# 11-Power.net
KiCad netlist of a schematic drawn in Altium Designer
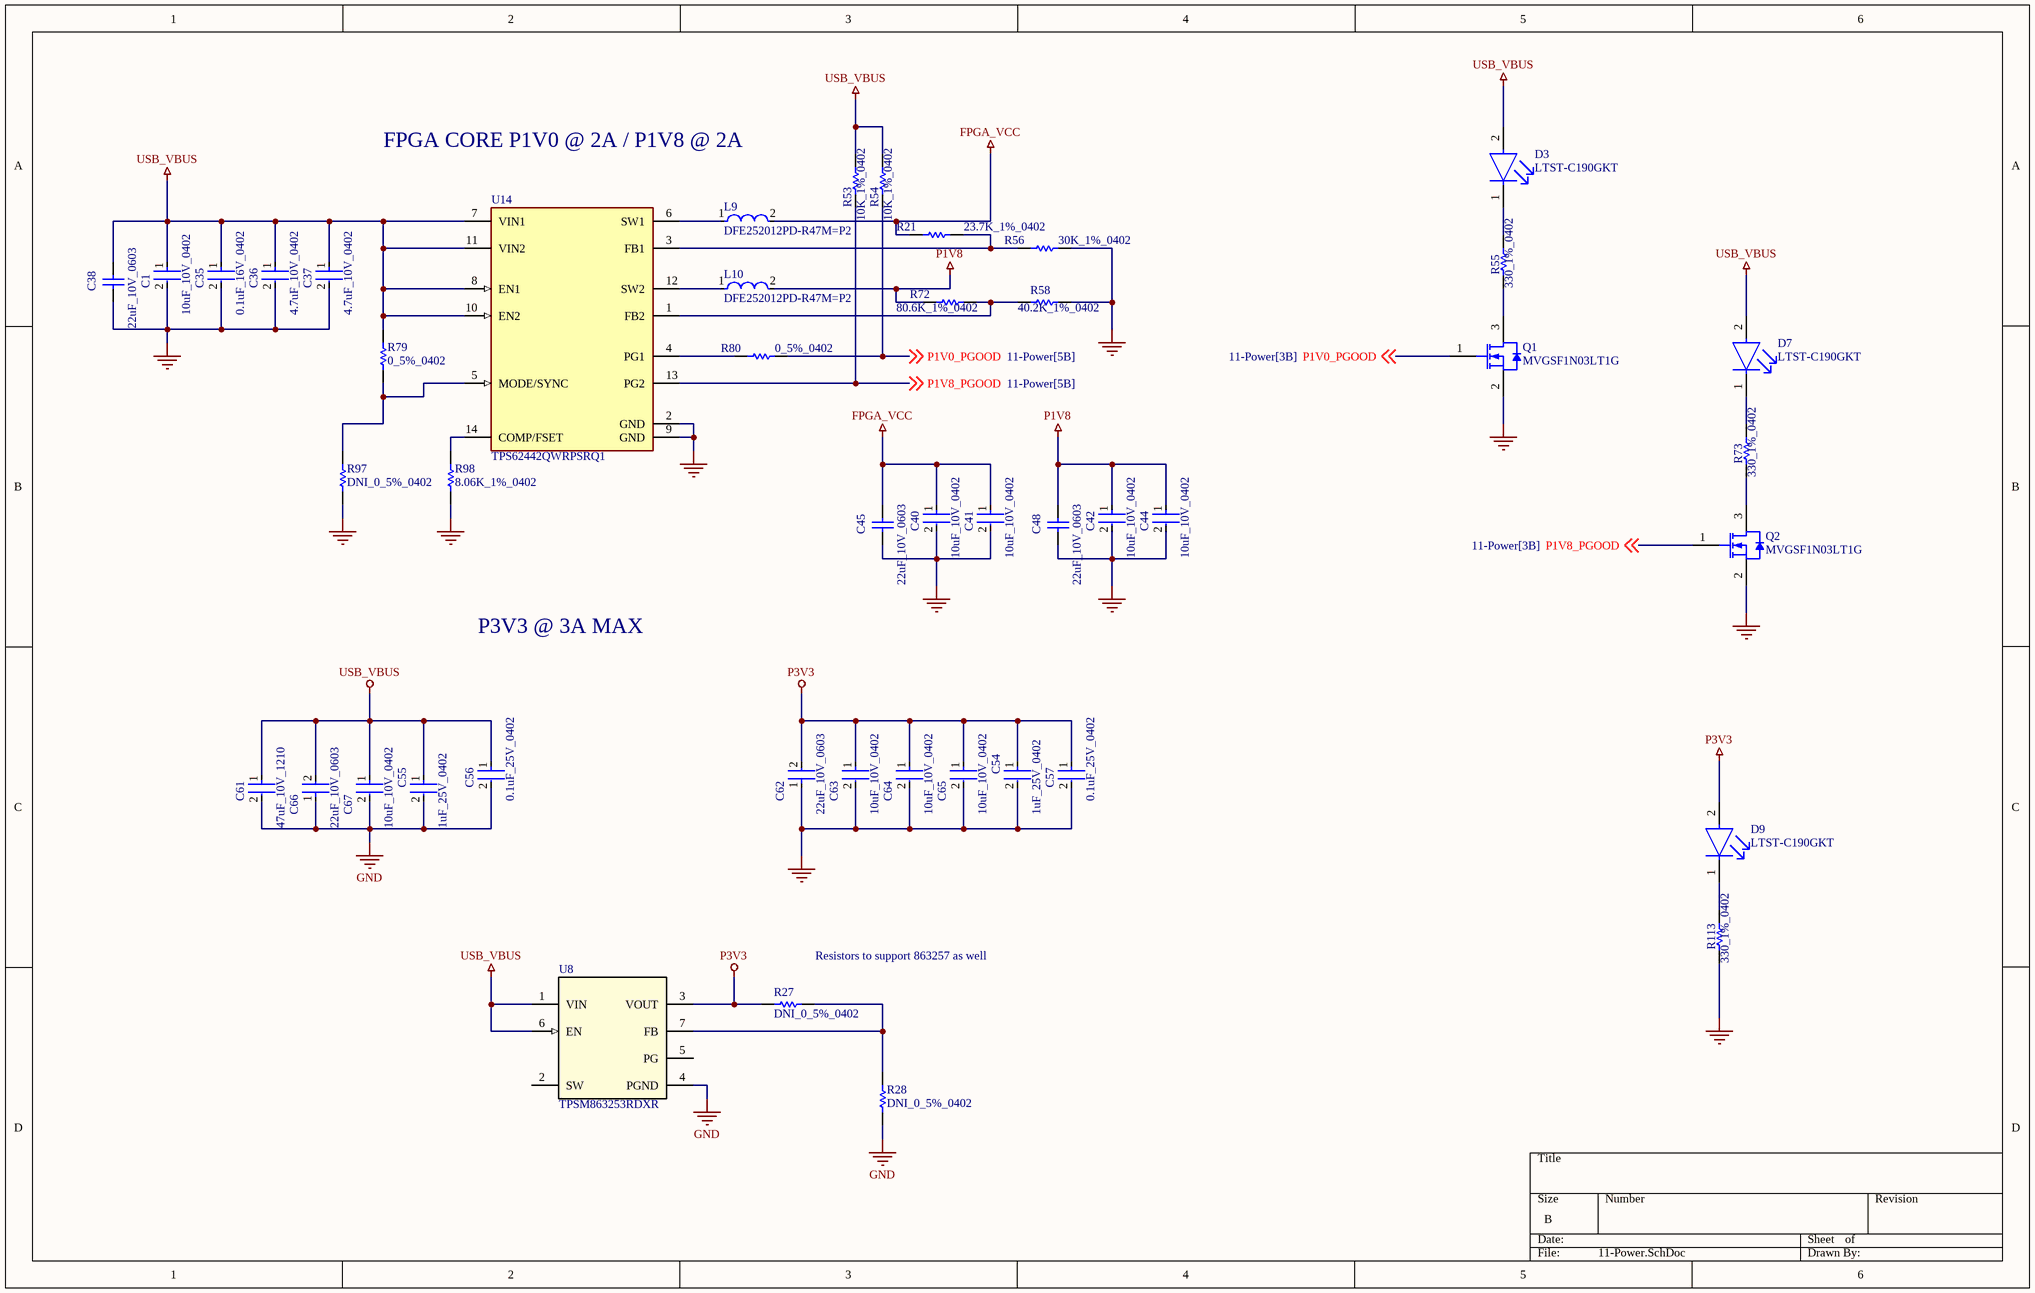
[diagram p0: 11-Power.SchDoc]

(export (version "E")
  (design (tool "Eeschema 10.0.6"))
  (components
    (comp (ref "C1")
      (value "10uF_10V_0402")
      (footprint "FP-CL05A106MP5NUNC-MFG")
      (description "CAP CER 10UF 10V X5R 0402")
      (fields
        (field (name "OCTOPART") "https://octopart.com/cl05a106mp5nunc-samsung-22457395")
        (field (name "TOLERANCE") "20%")
      )
      (libsource (lib "Altium Content Vault") (part "b4654b650e69147ec39a6b967a45e02"))
    )
    (comp (ref "C35")
      (value "0.1uF_16V_0402")
      (footprint "FP-C0402-BB-MFG")
      (description "CAP CER 0.1UF 16V 5% X7R 0402")
      (fields
        (field (name "MANUFACTURER") "Kemet")
        (field (name "MANUFACTURER PART NUMBER") "C0402C104J4RACTU")
      )
      (libsource (lib "Altium Content Vault") (part "b4654b650e69147ec39a6b967a45e02"))
    )
    (comp (ref "C36")
      (value "4.7uF_10V_0402")
      (footprint "FP-C1005-050-0_15-MFG")
      (description "CAP CER 4.7UF 10V X5R 0402")
      (fields (field (name "TOLERANCE") "10%"))
      (libsource (lib "Altium Content Vault") (part "b4654b650e69147ec39a6b967a45e02"))
    )
    (comp (ref "C37")
      (value "4.7uF_10V_0402")
      (footprint "FP-C1005-050-0_15-MFG")
      (description "CAP CER 4.7UF 10V X5R 0402")
      (fields (field (name "TOLERANCE") "10%"))
      (libsource (lib "Altium Content Vault") (part "b4654b650e69147ec39a6b967a45e02"))
    )
    (comp (ref "C38")
      (value "22uF_10V_0603")
      (footprint "CAPC1608X100X20ML10")
      (description "Chip Capacitor, 22 uF, +/- 20%, 10 V, -55 to 85 degC, 0603 (1608 Metric), RoHS, Tape and Reel")
      (fields (field (name "MANUFACTURER") "TDK") (field (name "TOLERANCE") "±20%"))
      (libsource (lib "Altium Content Vault") (part "CAP-NP-2"))
    )
    (comp (ref "C40")
      (value "10uF_10V_0402")
      (footprint "FP-CL05A106MP5NUNC-MFG")
      (description "CAP CER 10UF 10V X5R 0402")
      (fields
        (field (name "OCTOPART") "https://octopart.com/cl05a106mp5nunc-samsung-22457395")
        (field (name "TOLERANCE") "20%")
      )
      (libsource (lib "Altium Content Vault") (part "b4654b650e69147ec39a6b967a45e02"))
    )
    (comp (ref "C41")
      (value "10uF_10V_0402")
      (footprint "FP-CL05A106MP5NUNC-MFG")
      (description "CAP CER 10UF 10V X5R 0402")
      (fields
        (field (name "OCTOPART") "https://octopart.com/cl05a106mp5nunc-samsung-22457395")
        (field (name "TOLERANCE") "20%")
      )
      (libsource (lib "Altium Content Vault") (part "b4654b650e69147ec39a6b967a45e02"))
    )
    (comp (ref "C42")
      (value "10uF_10V_0402")
      (footprint "FP-CL05A106MP5NUNC-MFG")
      (description "CAP CER 10UF 10V X5R 0402")
      (fields
        (field (name "OCTOPART") "https://octopart.com/cl05a106mp5nunc-samsung-22457395")
        (field (name "TOLERANCE") "20%")
      )
      (libsource (lib "Altium Content Vault") (part "b4654b650e69147ec39a6b967a45e02"))
    )
    (comp (ref "C44")
      (value "10uF_10V_0402")
      (footprint "FP-CL05A106MP5NUNC-MFG")
      (description "CAP CER 10UF 10V X5R 0402")
      (fields
        (field (name "OCTOPART") "https://octopart.com/cl05a106mp5nunc-samsung-22457395")
        (field (name "TOLERANCE") "20%")
      )
      (libsource (lib "Altium Content Vault") (part "b4654b650e69147ec39a6b967a45e02"))
    )
    (comp (ref "C45")
      (value "22uF_10V_0603")
      (footprint "CAPC1608X100X20ML10")
      (description "Chip Capacitor, 22 uF, +/- 20%, 10 V, -55 to 85 degC, 0603 (1608 Metric), RoHS, Tape and Reel")
      (fields (field (name "MANUFACTURER") "TDK") (field (name "TOLERANCE") "±20%"))
      (libsource (lib "Altium Content Vault") (part "CAP-NP-2"))
    )
    (comp (ref "C48")
      (value "22uF_10V_0603")
      (footprint "CAPC1608X100X20ML10")
      (description "Chip Capacitor, 22 uF, +/- 20%, 10 V, -55 to 85 degC, 0603 (1608 Metric), RoHS, Tape and Reel")
      (fields (field (name "MANUFACTURER") "TDK") (field (name "TOLERANCE") "±20%"))
      (libsource (lib "Altium Content Vault") (part "CAP-NP-2"))
    )
    (comp (ref "C54")
      (value "1uF_25V_0402")
      (footprint "FP-C1005-050-0_05-IPC_B")
      (description "Multilayer Ceramic Capacitors 1μF ±10% 25V X5R SMD 0402")
      (fields (field (name "TOLERANCE") "10%"))
      (libsource (lib "Altium Content Vault") (part "b4654b650e69147ec39a6b967a45e02"))
    )
    (comp (ref "C55")
      (value "1uF_25V_0402")
      (footprint "FP-C1005-050-0_05-IPC_B")
      (description "Multilayer Ceramic Capacitors 1μF ±10% 25V X5R SMD 0402")
      (fields (field (name "TOLERANCE") "10%"))
      (libsource (lib "Altium Content Vault") (part "b4654b650e69147ec39a6b967a45e02"))
    )
    (comp (ref "C56")
      (value "0.1uF_25V_0402")
      (footprint "FP-0402-L_1_0_0_05-W_0_5-IPC_B")
      (description "None")
      (fields (field (name "TOLERANCE") "10%") (field (name "VOLTAGE") "25V"))
      (libsource (lib "Altium Content Vault") (part "b4654b650e69147ec39a6b967a45e02"))
    )
    (comp (ref "C57")
      (value "0.1uF_25V_0402")
      (footprint "FP-0402-L_1_0_0_05-W_0_5-IPC_B")
      (description "None")
      (fields (field (name "TOLERANCE") "10%") (field (name "VOLTAGE") "25V"))
      (libsource (lib "Altium Content Vault") (part "b4654b650e69147ec39a6b967a45e02"))
    )
    (comp (ref "C61")
      (value "47uF_10V_1210")
      (footprint "FP-MK325M-MFG")
      (description "CAP CER 47UF 10V X7R 1210")
      (fields (field (name "TOLERANCE") "20%") (field (name "VOLTAGE") "10V"))
      (libsource (lib "Altium Content Vault") (part "b4654b650e69147ec39a6b967a45e02"))
    )
    (comp (ref "C62")
      (value "22uF_10V_0603")
      (footprint "FP-GRM188-0_2-IPC_C")
      (description "Chip Multilayer Ceramic Capacitors for General Purpose, 0603, 22uF, X5R, 15%, 20%, 10V")
      (fields (field (name "TOLERANCE") "20%"))
      (libsource (lib "Altium Content Vault") (part "11868f565c42a9108669ba33697ecf6"))
    )
    (comp (ref "C63")
      (value "10uF_10V_0402")
      (footprint "FP-CL05A106MP5NUNC-MFG")
      (description "CAP CER 10UF 10V X5R 0402")
      (fields
        (field (name "OCTOPART") "https://octopart.com/cl05a106mp5nunc-samsung-22457395")
        (field (name "TOLERANCE") "20%")
      )
      (libsource (lib "Altium Content Vault") (part "b4654b650e69147ec39a6b967a45e02"))
    )
    (comp (ref "C64")
      (value "10uF_10V_0402")
      (footprint "FP-CL05A106MP5NUNC-MFG")
      (description "CAP CER 10UF 10V X5R 0402")
      (fields
        (field (name "OCTOPART") "https://octopart.com/cl05a106mp5nunc-samsung-22457395")
        (field (name "TOLERANCE") "20%")
      )
      (libsource (lib "Altium Content Vault") (part "b4654b650e69147ec39a6b967a45e02"))
    )
    (comp (ref "C65")
      (value "10uF_10V_0402")
      (footprint "FP-CL05A106MP5NUNC-MFG")
      (description "CAP CER 10UF 10V X5R 0402")
      (fields
        (field (name "OCTOPART") "https://octopart.com/cl05a106mp5nunc-samsung-22457395")
        (field (name "TOLERANCE") "20%")
      )
      (libsource (lib "Altium Content Vault") (part "b4654b650e69147ec39a6b967a45e02"))
    )
    (comp (ref "C66")
      (value "22uF_10V_0603")
      (footprint "FP-GRM188-0_2-IPC_C")
      (description "Chip Multilayer Ceramic Capacitors for General Purpose, 0603, 22uF, X5R, 15%, 20%, 10V")
      (fields (field (name "TOLERANCE") "20%"))
      (libsource (lib "Altium Content Vault") (part "11868f565c42a9108669ba33697ecf6"))
    )
    (comp (ref "C67")
      (value "10uF_10V_0402")
      (footprint "FP-CL05A106MP5NUNC-MFG")
      (description "CAP CER 10UF 10V X5R 0402")
      (fields
        (field (name "OCTOPART") "https://octopart.com/cl05a106mp5nunc-samsung-22457395")
        (field (name "TOLERANCE") "20%")
      )
      (libsource (lib "Altium Content Vault") (part "b4654b650e69147ec39a6b967a45e02"))
    )
    (comp (ref "D3")
      (value "LTST-C190GKT")
      (footprint "FP-LTST-C190GKT-MFG")
      (description "LED GREEN CLEAR CHIP SMD")
      (fields (field (name "VOLTAGE") "2V"))
      (libsource (lib "Altium Content Vault") (part "8706943c75ba83719d021d2fdc84c58"))
    )
    (comp (ref "D7")
      (value "LTST-C190GKT")
      (footprint "FP-LTST-C190GKT-MFG")
      (description "LED GREEN CLEAR CHIP SMD")
      (fields (field (name "VOLTAGE") "2V"))
      (libsource (lib "Altium Content Vault") (part "8706943c75ba83719d021d2fdc84c58"))
    )
    (comp (ref "D9")
      (value "LTST-C190GKT")
      (footprint "FP-LTST-C190GKT-MFG")
      (description "LED GREEN CLEAR CHIP SMD")
      (fields (field (name "VOLTAGE") "2V"))
      (libsource (lib "Altium Content Vault") (part "8706943c75ba83719d021d2fdc84c58"))
    )
    (comp (ref "L9")
      (value "DFE252012PD-R47M=P2")
      (footprint "FP-DFE252012C-IPC_A")
      (description "Shielded Wirewound Inductor 0.47uH 20% 4000mA 0.027Ω 1008 (2520)")
      (libsource (lib "Altium Content Vault") (part "725321dda6339637d4d059423bc1c3c"))
    )
    (comp (ref "L10")
      (value "DFE252012PD-R47M=P2")
      (footprint "FP-DFE252012C-IPC_A")
      (description "Shielded Wirewound Inductor 0.47uH 20% 4000mA 0.027Ω 1008 (2520)")
      (libsource (lib "Altium Content Vault") (part "725321dda6339637d4d059423bc1c3c"))
    )
    (comp (ref "Q1")
      (value "MVGSF1N03LT1G")
      (footprint "ONSC-SOT-23-3-318-08_V")
      (description "Power MOSFET, 30 V, 2.1 A, Single N-Channel, 3-Pin SOT-23, Pb-Free, Tape and Reel")
      (fields (field (name "MANUFACTURER") "On Semiconductor"))
      (libsource (lib "Altium Content Vault") (part "ONSC-NMOS-G1S2D3-3"))
    )
    (comp (ref "Q2")
      (value "MVGSF1N03LT1G")
      (footprint "ONSC-SOT-23-3-318-08_V")
      (description "Power MOSFET, 30 V, 2.1 A, Single N-Channel, 3-Pin SOT-23, Pb-Free, Tape and Reel")
      (fields (field (name "MANUFACTURER") "On Semiconductor"))
      (libsource (lib "Altium Content Vault") (part "ONSC-NMOS-G1S2D3-3"))
    )
    (comp (ref "R21")
      (value "23.7K_1%_0402")
      (footprint "RESC1005X40X25ML05T05")
      (fields (field (name "PART NUMBER") "CRCW040223K7FKED") (field (name "MANUFACTURER") "Vishay Dale"))
      (libsource (lib "Altium Content Vault") (part "RES"))
    )
    (comp (ref "R27")
      (value "DNI_0_5%_0402")
      (footprint "RESC1005X40X25NL05T10")
      (fields (field (name "MANUFACTURER") "Panasonic") (field (name "PART NUMBER") "ERJ-U020R00X"))
      (libsource (lib "Altium Content Vault") (part "RES"))
    )
    (comp (ref "R28")
      (value "DNI_0_5%_0402")
      (footprint "RESC1005X40X25NL05T10")
      (fields (field (name "MANUFACTURER") "Panasonic") (field (name "PART NUMBER") "ERJ-U020R00X"))
      (libsource (lib "Altium Content Vault") (part "RES"))
    )
    (comp (ref "R53")
      (value "10K_1%_0402")
      (footprint "RESC1005X40X25NL10T10")
      (fields (field (name "MANUFACTURER") "Bourns") (field (name "PART NUMBER") "CR0402-FX-1002GLF"))
      (libsource (lib "Altium Content Vault") (part "RES"))
    )
    (comp (ref "R54")
      (value "10K_1%_0402")
      (footprint "RESC1005X40X25NL10T10")
      (fields (field (name "MANUFACTURER") "Bourns") (field (name "PART NUMBER") "CR0402-FX-1002GLF"))
      (libsource (lib "Altium Content Vault") (part "RES"))
    )
    (comp (ref "R55")
      (value "330_1%_0402")
      (footprint "RESC1005X40X25NL10T10")
      (fields (field (name "MANUFACTURER") "Panasonic") (field (name "PART NUMBER") "ERA-2AED331X"))
      (libsource (lib "Altium Content Vault") (part "RES"))
    )
    (comp (ref "R56")
      (value "30K_1%_0402")
      (footprint "RESC1005X40X25ML05T05")
      (fields (field (name "PART NUMBER") "ERJ-2GEJ303X") (field (name "MANUFACTURER") "Panasonic"))
      (libsource (lib "Altium Content Vault") (part "RES"))
    )
    (comp (ref "R58")
      (value "40.2K_1%_0402")
      (footprint "RESC1005X40X25ML05T10")
      (fields (field (name "PART NUMBER") "RC0402FR-0740K2L") (field (name "MANUFACTURER") "Yageo / Phycomp"))
      (libsource (lib "Altium Content Vault") (part "RES"))
    )
    (comp (ref "R72")
      (value "80.6K_1%_0402")
      (footprint "RESC1005X40X25NL05T10")
      (fields (field (name "PART NUMBER") "RC0402FR-0780K6L") (field (name "MANUFACTURER") "Yageo / Phycomp"))
      (libsource (lib "Altium Content Vault") (part "RES"))
    )
    (comp (ref "R73")
      (value "330_1%_0402")
      (footprint "RESC1005X40X25NL10T10")
      (fields (field (name "MANUFACTURER") "Panasonic") (field (name "PART NUMBER") "ERA-2AED331X"))
      (libsource (lib "Altium Content Vault") (part "RES"))
    )
    (comp (ref "R79")
      (value "0_5%_0402")
      (footprint "RESC1005X40X25NL05T10")
      (fields (field (name "MANUFACTURER") "Panasonic") (field (name "PART NUMBER") "ERJ-U020R00X"))
      (libsource (lib "Altium Content Vault") (part "RES"))
    )
    (comp (ref "R80")
      (value "0_5%_0402")
      (footprint "RESC1005X40X25NL05T10")
      (fields (field (name "MANUFACTURER") "Panasonic") (field (name "PART NUMBER") "ERJ-U020R00X"))
      (libsource (lib "Altium Content Vault") (part "RES"))
    )
    (comp (ref "R97")
      (value "DNI_0_5%_0402")
      (footprint "RESC1005X40X25NL05T10")
      (fields (field (name "MANUFACTURER") "Panasonic") (field (name "PART NUMBER") "ERJ-U020R00X"))
      (libsource (lib "Altium Content Vault") (part "RES"))
    )
    (comp (ref "R98")
      (value "8.06K_1%_0402")
      (footprint "RESC1005X40X25ML05T05")
      (description "Chip Resistor, 8.06 KOhm, +/- 1%, 63 mW, -55 to 155 degC, 0402 (1005 Metric), RoHS, Tape and Reel")
      (fields (field (name "PARTNUMBER") "CRCW04028K06FKED") (field (name "TOLERANCE") "1%"))
      (libsource (lib "Altium Content Vault") (part "RES-2"))
    )
    (comp (ref "R113")
      (value "330_1%_0402")
      (footprint "RESC1005X40X25NL10T10")
      (fields (field (name "MANUFACTURER") "Panasonic") (field (name "PART NUMBER") "ERA-2AED331X"))
      (libsource (lib "Altium Content Vault") (part "RES"))
    )
    (comp (ref "U8")
      (value "TPSM863253RDXR")
      (footprint "RDX0007A-MFG")
      (description "No Description Available")
      (libsource (lib "TPSM863253RDXR") (part "TPSM863253RDXR"))
    )
    (comp (ref "U14")
      (value "TPS62442QWRPSRQ1")
      (footprint "FP-RQR0014A-MFG")
      (description "Adjustable-Frequency Dual Step-Down Converter, 2.7-6V VIN, 0.6-5.5V 2A VOUT, VQFN-HR14")
      (libsource (lib "Altium Content Vault") (part "72c5b9bb22caeb688b1070b758806aa"))
    )
  )
  (nets
    (net (code "1") (name "FPGA_VCC") (class "Default")
      (node (ref "C40") (pin "1") (pinfunction "1_1") (pintype "passive"))
      (node (ref "C41") (pin "1") (pinfunction "1_1") (pintype "passive"))
      (node (ref "C45") (pin "2") (pinfunction "2_2") (pintype "passive"))
      (node (ref "L9") (pin "2") (pinfunction "2_2") (pintype "passive"))
      (node (ref "R21") (pin "1") (pinfunction "1_1") (pintype "passive"))
    )
    (net (code "2") (name "GND") (class "Default")
      (node (ref "C1") (pin "2") (pinfunction "2_2") (pintype "passive"))
      (node (ref "C35") (pin "2") (pinfunction "2_2") (pintype "passive"))
      (node (ref "C36") (pin "2") (pinfunction "2_2") (pintype "passive"))
      (node (ref "C37") (pin "2") (pinfunction "2_2") (pintype "passive"))
      (node (ref "C38") (pin "1") (pinfunction "1_1") (pintype "passive"))
      (node (ref "C40") (pin "2") (pinfunction "2_2") (pintype "passive"))
      (node (ref "C41") (pin "2") (pinfunction "2_2") (pintype "passive"))
      (node (ref "C42") (pin "2") (pinfunction "2_2") (pintype "passive"))
      (node (ref "C44") (pin "2") (pinfunction "2_2") (pintype "passive"))
      (node (ref "C45") (pin "1") (pinfunction "1_1") (pintype "passive"))
      (node (ref "C48") (pin "1") (pinfunction "1_1") (pintype "passive"))
      (node (ref "C54") (pin "2") (pinfunction "2_2") (pintype "passive"))
      (node (ref "C55") (pin "2") (pinfunction "2_2") (pintype "passive"))
      (node (ref "C56") (pin "2") (pinfunction "2_2") (pintype "passive"))
      (node (ref "C57") (pin "2") (pinfunction "2_2") (pintype "passive"))
      (node (ref "C61") (pin "2") (pinfunction "2_2") (pintype "passive"))
      (node (ref "C62") (pin "1") (pinfunction "1_1") (pintype "passive"))
      (node (ref "C63") (pin "2") (pinfunction "2_2") (pintype "passive"))
      (node (ref "C64") (pin "2") (pinfunction "2_2") (pintype "passive"))
      (node (ref "C65") (pin "2") (pinfunction "2_2") (pintype "passive"))
      (node (ref "C66") (pin "1") (pinfunction "1_1") (pintype "passive"))
      (node (ref "C67") (pin "2") (pinfunction "2_2") (pintype "passive"))
      (node (ref "Q1") (pin "2") (pinfunction "S_2") (pintype "passive"))
      (node (ref "Q2") (pin "2") (pinfunction "S_2") (pintype "passive"))
      (node (ref "R113") (pin "1") (pinfunction "1_1") (pintype "passive"))
      (node (ref "R28") (pin "2") (pinfunction "2_2") (pintype "passive"))
      (node (ref "R56") (pin "2") (pinfunction "2_2") (pintype "passive"))
      (node (ref "R58") (pin "2") (pinfunction "2_2") (pintype "passive"))
      (node (ref "R97") (pin "1") (pinfunction "1_1") (pintype "passive"))
      (node (ref "R98") (pin "1") (pinfunction "1_1") (pintype "passive"))
      (node (ref "U14") (pin "2") (pinfunction "GND_2") (pintype "power_in"))
      (node (ref "U14") (pin "9") (pinfunction "GND_9") (pintype "power_in"))
      (node (ref "U8") (pin "4") (pinfunction "PGND_4") (pintype "power_in"))
    )
    (net (code "3") (name "Net-(D3-C)") (class "Default")
      (node (ref "D3") (pin "1") (pinfunction "C_1") (pintype "passive"))
      (node (ref "R55") (pin "2") (pinfunction "2_2") (pintype "passive"))
    )
    (net (code "4") (name "Net-(D7-C)") (class "Default")
      (node (ref "D7") (pin "1") (pinfunction "C_1") (pintype "passive"))
      (node (ref "R73") (pin "2") (pinfunction "2_2") (pintype "passive"))
    )
    (net (code "5") (name "Net-(D9-C)") (class "Default")
      (node (ref "D9") (pin "1") (pinfunction "C_1") (pintype "passive"))
      (node (ref "R113") (pin "2") (pinfunction "2_2") (pintype "passive"))
    )
    (net (code "6") (name "Net-(Q1-D)") (class "Default")
      (node (ref "Q1") (pin "3") (pinfunction "D_3") (pintype "passive"))
      (node (ref "R55") (pin "1") (pinfunction "1_1") (pintype "passive"))
    )
    (net (code "7") (name "Net-(Q2-D)") (class "Default")
      (node (ref "Q2") (pin "3") (pinfunction "D_3") (pintype "passive"))
      (node (ref "R73") (pin "1") (pinfunction "1_1") (pintype "passive"))
    )
    (net (code "8") (name "Net-(U8-FB)") (class "Default")
      (node (ref "R27") (pin "1") (pinfunction "1_1") (pintype "passive"))
      (node (ref "R28") (pin "1") (pinfunction "1_1") (pintype "passive"))
      (node (ref "U8") (pin "7") (pinfunction "FB_7") (pintype "passive"))
    )
    (net (code "9") (name "Net-(U14-COMP{slash}FSET)") (class "Default")
      (node (ref "R98") (pin "2") (pinfunction "2_2") (pintype "passive"))
      (node (ref "U14") (pin "14") (pinfunction "COMP/FSET_14") (pintype "passive"))
    )
    (net (code "10") (name "Net-(U14-FB1)") (class "Default")
      (node (ref "R21") (pin "2") (pinfunction "2_2") (pintype "passive"))
      (node (ref "R56") (pin "1") (pinfunction "1_1") (pintype "passive"))
      (node (ref "U14") (pin "3") (pinfunction "FB1_3") (pintype "passive"))
    )
    (net (code "11") (name "Net-(U14-FB2)") (class "Default")
      (node (ref "R58") (pin "1") (pinfunction "1_1") (pintype "passive"))
      (node (ref "R72") (pin "2") (pinfunction "2_2") (pintype "passive"))
      (node (ref "U14") (pin "1") (pinfunction "FB2_1") (pintype "passive"))
    )
    (net (code "12") (name "Net-(U14-MODE{slash}SYNC)") (class "Default")
      (node (ref "R79") (pin "1") (pinfunction "1_1") (pintype "passive"))
      (node (ref "R97") (pin "2") (pinfunction "2_2") (pintype "passive"))
      (node (ref "U14") (pin "5") (pinfunction "MODE/SYNC_5") (pintype "input"))
    )
    (net (code "13") (name "Net-(U14-PG1)") (class "Default")
      (node (ref "R80") (pin "1") (pinfunction "1_1") (pintype "passive"))
      (node (ref "U14") (pin "4") (pinfunction "PG1_4") (pintype "open_collector"))
    )
    (net (code "14") (name "Net-(U14-SW1)") (class "Default")
      (node (ref "L9") (pin "1") (pinfunction "1_1") (pintype "passive"))
      (node (ref "U14") (pin "6") (pinfunction "SW1_6") (pintype "passive"))
    )
    (net (code "15") (name "Net-(U14-SW2)") (class "Default")
      (node (ref "L10") (pin "1") (pinfunction "1_1") (pintype "passive"))
      (node (ref "U14") (pin "12") (pinfunction "SW2_12") (pintype "passive"))
    )
    (net (code "16") (name "P1V0_PGOOD") (class "Default")
      (node (ref "Q1") (pin "1") (pinfunction "G_1") (pintype "passive"))
      (node (ref "R54") (pin "1") (pinfunction "1_1") (pintype "passive"))
      (node (ref "R80") (pin "2") (pinfunction "2_2") (pintype "passive"))
    )
    (net (code "17") (name "P1V8") (class "Default")
      (node (ref "C42") (pin "1") (pinfunction "1_1") (pintype "passive"))
      (node (ref "C44") (pin "1") (pinfunction "1_1") (pintype "passive"))
      (node (ref "C48") (pin "2") (pinfunction "2_2") (pintype "passive"))
      (node (ref "L10") (pin "2") (pinfunction "2_2") (pintype "passive"))
      (node (ref "R72") (pin "1") (pinfunction "1_1") (pintype "passive"))
    )
    (net (code "18") (name "P1V8_PGOOD") (class "Default")
      (node (ref "Q2") (pin "1") (pinfunction "G_1") (pintype "passive"))
      (node (ref "R53") (pin "1") (pinfunction "1_1") (pintype "passive"))
      (node (ref "U14") (pin "13") (pinfunction "PG2_13") (pintype "open_collector"))
    )
    (net (code "19") (name "P3V3") (class "Default")
      (node (ref "C54") (pin "1") (pinfunction "1_1") (pintype "passive"))
      (node (ref "C57") (pin "1") (pinfunction "1_1") (pintype "passive"))
      (node (ref "C62") (pin "2") (pinfunction "2_2") (pintype "passive"))
      (node (ref "C63") (pin "1") (pinfunction "1_1") (pintype "passive"))
      (node (ref "C64") (pin "1") (pinfunction "1_1") (pintype "passive"))
      (node (ref "C65") (pin "1") (pinfunction "1_1") (pintype "passive"))
      (node (ref "D9") (pin "2") (pinfunction "A_2") (pintype "passive"))
      (node (ref "R27") (pin "2") (pinfunction "2_2") (pintype "passive"))
      (node (ref "U8") (pin "3") (pinfunction "VOUT_3") (pintype "power_in"))
    )
    (net (code "20") (name "USB_VBUS") (class "Default")
      (node (ref "C1") (pin "1") (pinfunction "1_1") (pintype "passive"))
      (node (ref "C35") (pin "1") (pinfunction "1_1") (pintype "passive"))
      (node (ref "C36") (pin "1") (pinfunction "1_1") (pintype "passive"))
      (node (ref "C37") (pin "1") (pinfunction "1_1") (pintype "passive"))
      (node (ref "C38") (pin "2") (pinfunction "2_2") (pintype "passive"))
      (node (ref "C55") (pin "1") (pinfunction "1_1") (pintype "passive"))
      (node (ref "C56") (pin "1") (pinfunction "1_1") (pintype "passive"))
      (node (ref "C61") (pin "1") (pinfunction "1_1") (pintype "passive"))
      (node (ref "C66") (pin "2") (pinfunction "2_2") (pintype "passive"))
      (node (ref "C67") (pin "1") (pinfunction "1_1") (pintype "passive"))
      (node (ref "D3") (pin "2") (pinfunction "A_2") (pintype "passive"))
      (node (ref "D7") (pin "2") (pinfunction "A_2") (pintype "passive"))
      (node (ref "R53") (pin "2") (pinfunction "2_2") (pintype "passive"))
      (node (ref "R54") (pin "2") (pinfunction "2_2") (pintype "passive"))
      (node (ref "R79") (pin "2") (pinfunction "2_2") (pintype "passive"))
      (node (ref "U14") (pin "10") (pinfunction "EN2_10") (pintype "input"))
      (node (ref "U14") (pin "11") (pinfunction "VIN2_11") (pintype "power_in"))
      (node (ref "U14") (pin "7") (pinfunction "VIN1_7") (pintype "power_in"))
      (node (ref "U14") (pin "8") (pinfunction "EN1_8") (pintype "input"))
      (node (ref "U8") (pin "1") (pinfunction "VIN_1") (pintype "power_in"))
      (node (ref "U8") (pin "6") (pinfunction "EN_6") (pintype "input"))
    )
    (net (code "21") (name "unconnected-(U8-PG-Pad5)") (class "Default")
      (node (ref "U8") (pin "5") (pinfunction "PG_5") (pintype "open_collector"))
    )
    (net (code "22") (name "unconnected-(U8-SW-Pad2)") (class "Default")
      (node (ref "U8") (pin "2") (pinfunction "SW_2") (pintype "passive"))
    )
  )
)
